# Sheet1.net
KiCad netlist of a schematic drawn in Altium Designer
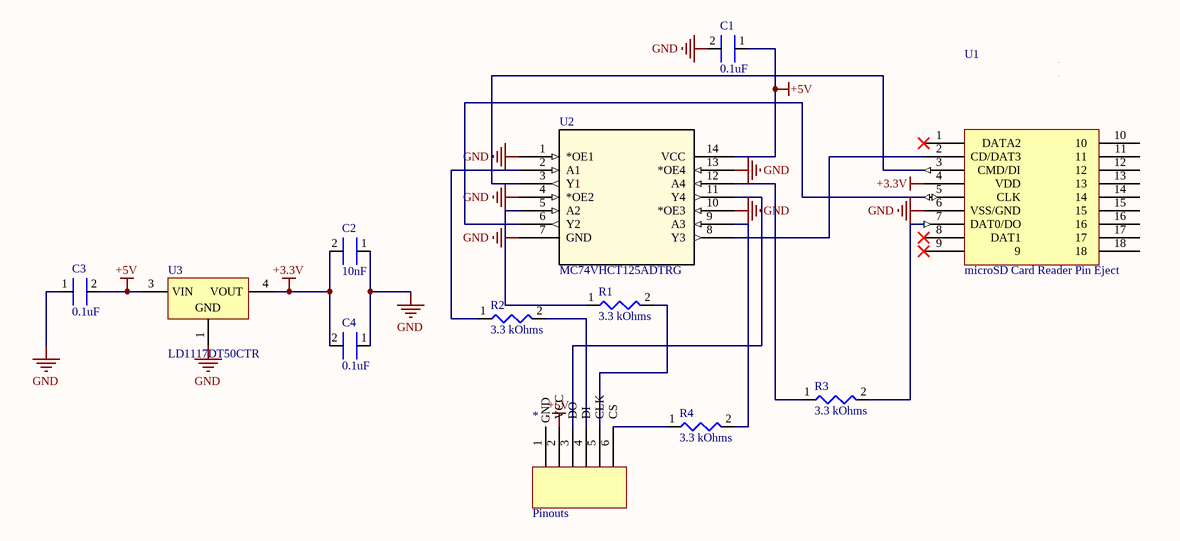
[diagram p0: Sheet1.SchDoc]

(export (version "E")
  (design (tool "Eeschema 10.0.6"))
  (components
    (comp (ref "*") (value "Pinouts") (libsource (lib "Schlib1") (part "Pinouts")))
    (comp (ref "C1")
      (value "0.1uF")
      (footprint "CAPC2012X14N_1_35mm_HEIGHT")
      (description "Capacitor Multilayer Ceramic MLCC - SMD/SMT 25 V 0.1uF X7R 0805 5%")
      (fields
        (field (name "MANUFACTURER") "Yageo")
        (field (name "MANUFACTURER PART NUMBER") "CC0805JPX7R8BB104")
      )
      (libsource (lib "Schlib1") (part "CC0805JPX7R8BB104"))
    )
    (comp (ref "C2")
      (value "10nF")
      (footprint "CAPC2012X07N_06mmHEIGHT")
      (description "Capacitor Multilayer Ceramic MLCC - SMD/SMT 50V 10nF X7R 0805 5%")
      (fields
        (field (name "MANUFACTURER") "Yageo")
        (field (name "MANUFACTURER PART NUMBER") "CC0805JRX7R9BB103")
      )
      (libsource (lib "Schlib1") (part "CC0805JRX7R9BB103"))
    )
    (comp (ref "C3")
      (value "0.1uF")
      (footprint "CAPC2012X14N_1_35mm_HEIGHT")
      (description "Capacitor Multilayer Ceramic MLCC - SMD/SMT 25 V 0.1uF X7R 0805 5%")
      (fields
        (field (name "MANUFACTURER") "Yageo")
        (field (name "MANUFACTURER PART NUMBER") "CC0805JPX7R8BB104")
      )
      (libsource (lib "Schlib1") (part "CC0805JPX7R8BB104"))
    )
    (comp (ref "C4")
      (value "0.1uF")
      (footprint "CAPC2012X14N_1_35mm_HEIGHT")
      (description "Capacitor Multilayer Ceramic MLCC - SMD/SMT 25 V 0.1uF X7R 0805 5%")
      (fields
        (field (name "MANUFACTURER") "Yageo")
        (field (name "MANUFACTURER PART NUMBER") "CC0805JPX7R8BB104")
      )
      (libsource (lib "Schlib1") (part "CC0805JPX7R8BB104"))
    )
    (comp (ref "R1")
      (value "3.3 kOhms")
      (footprint "RESC2012X06N")
      (description "3.3 kOhms ±1% 0.25W, 1/4W Chip Resistor 0805 (2012 Metric) Moisture Resistant Thick Film")
      (fields
        (field (name "MANUFACTURER") "Yageo")
        (field (name "MANUFACTURER PART NUMBER") "RC0805FR-7W3K3L")
      )
      (libsource (lib "Schlib1") (part "RC0805FR-7W3K3L Yageo"))
    )
    (comp (ref "R2")
      (value "3.3 kOhms")
      (footprint "RESC2012X06N")
      (description "3.3 kOhms ±1% 0.25W, 1/4W Chip Resistor 0805 (2012 Metric) Moisture Resistant Thick Film")
      (fields
        (field (name "MANUFACTURER") "Yageo")
        (field (name "MANUFACTURER PART NUMBER") "RC0805FR-7W3K3L")
      )
      (libsource (lib "Schlib1") (part "RC0805FR-7W3K3L Yageo"))
    )
    (comp (ref "R3")
      (value "3.3 kOhms")
      (footprint "RESC2012X06N")
      (description "3.3 kOhms ±1% 0.25W, 1/4W Chip Resistor 0805 (2012 Metric) Moisture Resistant Thick Film")
      (fields
        (field (name "MANUFACTURER") "Yageo")
        (field (name "MANUFACTURER PART NUMBER") "RC0805FR-7W3K3L")
      )
      (libsource (lib "Schlib1") (part "RC0805FR-7W3K3L Yageo"))
    )
    (comp (ref "R4")
      (value "3.3 kOhms")
      (footprint "RESC2012X06N")
      (description "3.3 kOhms ±1% 0.25W, 1/4W Chip Resistor 0805 (2012 Metric) Moisture Resistant Thick Film")
      (fields
        (field (name "MANUFACTURER") "Yageo")
        (field (name "MANUFACTURER PART NUMBER") "RC0805FR-7W3K3L")
      )
      (libsource (lib "Schlib1") (part "RC0805FR-7W3K3L Yageo"))
    )
    (comp (ref "U1")
      (value "microSD Card Reader Pin Eject")
      (fields
        (field (name "MANUFACTURER") "Molex")
        (field (name "MANUFACTURER PART NUMBER") "504528-0892-CUT-TAPE")
      )
      (libsource (lib "Schlib1") (part "504528-0892"))
    )
    (comp (ref "U2")
      (value "MC74VHCT125ADTRG")
      (footprint "TSSOP14_4P50X5P10_ONS")
      (description "Bus Driver, AHCT/VHCT Series, 4-Func, 1-Bit, True Output, CMOS, PDSO14")
      (fields (field (name "MANUFACTURER") "ON Semiconductor"))
      (libsource (lib "Schlib1") (part "MC74VHCT125ADTRG"))
    )
    (comp (ref "U3")
      (value "LD1117DT50CTR")
      (footprint "TO-252_M")
      (description "Fixed Low Drop Positive Voltage Regulator, 5V, 3-Pin DPAK, Tape and Reel")
      (libsource (lib "Schlib1") (part "CMP-0244-00109-1"))
    )
  )
  (nets
    (net (code "1") (name "+3.3V") (class "Default")
      (node (ref "C2") (pin "2") (pinfunction "2_2") (pintype "passive"))
      (node (ref "C4") (pin "2") (pinfunction "2_2") (pintype "passive"))
      (node (ref "U3") (pin "4") (pinfunction "VOUT_4") (pintype "power_in"))
    )
    (net (code "2") (name "+5V") (class "Default")
      (node (ref "C1") (pin "1") (pinfunction "1_1") (pintype "passive"))
      (node (ref "C3") (pin "2") (pinfunction "2_2") (pintype "passive"))
      (node (ref "U2") (pin "14") (pinfunction "VCC_14") (pintype "power_in"))
      (node (ref "U3") (pin "3") (pinfunction "VIN_3") (pintype "power_in"))
    )
    (net (code "3") (name "GND") (class "Default")
      (node (ref "C1") (pin "2") (pinfunction "2_2") (pintype "passive"))
      (node (ref "C2") (pin "1") (pinfunction "1_1") (pintype "passive"))
      (node (ref "C3") (pin "1") (pinfunction "1_1") (pintype "passive"))
      (node (ref "C4") (pin "1") (pinfunction "1_1") (pintype "passive"))
      (node (ref "U2") (pin "1") (pinfunction "*OE1_1") (pintype "input"))
      (node (ref "U2") (pin "10") (pinfunction "*OE3_10") (pintype "input"))
      (node (ref "U2") (pin "13") (pinfunction "*OE4_13") (pintype "input"))
      (node (ref "U2") (pin "4") (pinfunction "*OE2_4") (pintype "input"))
      (node (ref "U2") (pin "7") (pinfunction "GND_7") (pintype "power_in"))
      (node (ref "U3") (pin "1") (pinfunction "GND_1") (pintype "power_in"))
    )
    (net (code "4") (name "Net-(U2-A1)") (class "Default")
      (node (ref "R2") (pin "1") (pinfunction "1_1") (pintype "passive"))
      (node (ref "U2") (pin "2") (pinfunction "A1_2") (pintype "input"))
    )
    (net (code "5") (name "Net-(U2-A2)") (class "Default")
      (node (ref "R1") (pin "1") (pinfunction "1_1") (pintype "passive"))
      (node (ref "U2") (pin "5") (pinfunction "A2_5") (pintype "input"))
    )
    (net (code "6") (name "Net-(U2-A3)") (class "Default")
      (node (ref "R4") (pin "2") (pinfunction "2_2") (pintype "passive"))
      (node (ref "U2") (pin "9") (pinfunction "A3_9") (pintype "input"))
    )
    (net (code "7") (name "Net-(U2-A4)") (class "Default")
      (node (ref "R3") (pin "1") (pinfunction "1_1") (pintype "passive"))
      (node (ref "U2") (pin "12") (pinfunction "A4_12") (pintype "input"))
    )
    (net (code "8") (name "unconnected-(*-CLK-Pad5)") (class "Default")
      (node (ref "*") (pin "5") (pinfunction "CLK_5") (pintype "passive"))
    )
    (net (code "9") (name "unconnected-(*-CS-Pad6)") (class "Default")
      (node (ref "*") (pin "6") (pinfunction "CS_6") (pintype "passive"))
    )
    (net (code "10") (name "unconnected-(*-DI-Pad4)") (class "Default")
      (node (ref "*") (pin "4") (pinfunction "DI_4") (pintype "passive"))
    )
    (net (code "11") (name "unconnected-(*-DO-Pad3)") (class "Default")
      (node (ref "*") (pin "3") (pinfunction "DO_3") (pintype "passive"))
    )
    (net (code "12") (name "unconnected-(*-GND-Pad1)") (class "Default")
      (node (ref "*") (pin "1") (pinfunction "GND_1") (pintype "passive"))
    )
    (net (code "13") (name "unconnected-(*-VCC-Pad2)") (class "Default")
      (node (ref "*") (pin "2") (pinfunction "VCC_2") (pintype "passive"))
    )
    (net (code "14") (name "unconnected-(R1-Pad2)") (class "Default")
      (node (ref "R1") (pin "2") (pinfunction "2_2") (pintype "passive"))
    )
    (net (code "15") (name "unconnected-(R2-Pad2)") (class "Default")
      (node (ref "R2") (pin "2") (pinfunction "2_2") (pintype "passive"))
    )
    (net (code "16") (name "unconnected-(R3-Pad2)") (class "Default")
      (node (ref "R3") (pin "2") (pinfunction "2_2") (pintype "passive"))
    )
    (net (code "17") (name "unconnected-(R4-Pad1)") (class "Default")
      (node (ref "R4") (pin "1") (pinfunction "1_1") (pintype "passive"))
    )
    (net (code "18") (name "unconnected-(U1-CD{slash}DAT3-Pad2)") (class "Default")
      (node (ref "U1") (pin "2") (pinfunction "CD/DAT3_2") (pintype "passive"))
    )
    (net (code "19") (name "unconnected-(U1-CLK-Pad5)") (class "Default")
      (node (ref "U1") (pin "5") (pinfunction "CLK_5") (pintype "bidirectional"))
    )
    (net (code "20") (name "unconnected-(U1-CMD{slash}DI-Pad3)") (class "Default")
      (node (ref "U1") (pin "3") (pinfunction "CMD/DI_3") (pintype "input"))
    )
    (net (code "21") (name "unconnected-(U1-DAT0{slash}DO-Pad7)") (class "Default")
      (node (ref "U1") (pin "7") (pinfunction "DAT0/DO_7") (pintype "output"))
    )
    (net (code "22") (name "unconnected-(U1-DAT1-Pad8)") (class "Default")
      (node (ref "U1") (pin "8") (pinfunction "DAT1_8") (pintype "passive"))
    )
    (net (code "23") (name "unconnected-(U1-DATA2-Pad1)") (class "Default")
      (node (ref "U1") (pin "1") (pinfunction "DATA2_1") (pintype "passive"))
    )
    (net (code "24") (name "unconnected-(U1-Pad9)") (class "Default")
      (node (ref "U1") (pin "9") (pinfunction "9_9") (pintype "passive"))
    )
    (net (code "25") (name "unconnected-(U1-Pad10)") (class "Default")
      (node (ref "U1") (pin "10") (pinfunction "10_10") (pintype "passive"))
    )
    (net (code "26") (name "unconnected-(U1-Pad11)") (class "Default")
      (node (ref "U1") (pin "11") (pinfunction "11_11") (pintype "passive"))
    )
    (net (code "27") (name "unconnected-(U1-Pad12)") (class "Default")
      (node (ref "U1") (pin "12") (pinfunction "12_12") (pintype "passive"))
    )
    (net (code "28") (name "unconnected-(U1-Pad13)") (class "Default")
      (node (ref "U1") (pin "13") (pinfunction "13_13") (pintype "passive"))
    )
    (net (code "29") (name "unconnected-(U1-Pad14)") (class "Default")
      (node (ref "U1") (pin "14") (pinfunction "14_14") (pintype "passive"))
    )
    (net (code "30") (name "unconnected-(U1-Pad15)") (class "Default")
      (node (ref "U1") (pin "15") (pinfunction "15_15") (pintype "passive"))
    )
    (net (code "31") (name "unconnected-(U1-Pad16)") (class "Default")
      (node (ref "U1") (pin "16") (pinfunction "16_16") (pintype "passive"))
    )
    (net (code "32") (name "unconnected-(U1-Pad17)") (class "Default")
      (node (ref "U1") (pin "17") (pinfunction "17_17") (pintype "passive"))
    )
    (net (code "33") (name "unconnected-(U1-Pad18)") (class "Default")
      (node (ref "U1") (pin "18") (pinfunction "18_18") (pintype "passive"))
    )
    (net (code "34") (name "unconnected-(U1-VDD-Pad4)") (class "Default")
      (node (ref "U1") (pin "4") (pinfunction "VDD_4") (pintype "power_in"))
    )
    (net (code "35") (name "unconnected-(U1-VSS{slash}GND-Pad6)") (class "Default")
      (node (ref "U1") (pin "6") (pinfunction "VSS/GND_6") (pintype "power_in"))
    )
    (net (code "36") (name "unconnected-(U2-Y1-Pad3)") (class "Default")
      (node (ref "U2") (pin "3") (pinfunction "Y1_3") (pintype "output"))
    )
    (net (code "37") (name "unconnected-(U2-Y2-Pad6)") (class "Default")
      (node (ref "U2") (pin "6") (pinfunction "Y2_6") (pintype "output"))
    )
    (net (code "38") (name "unconnected-(U2-Y3-Pad8)") (class "Default")
      (node (ref "U2") (pin "8") (pinfunction "Y3_8") (pintype "output"))
    )
    (net (code "39") (name "unconnected-(U2-Y4-Pad11)") (class "Default")
      (node (ref "U2") (pin "11") (pinfunction "Y4_11") (pintype "output"))
    )
  )
)
